# shift_register_pcb.net
KiCad netlist of a schematic drawn in Altium Designer
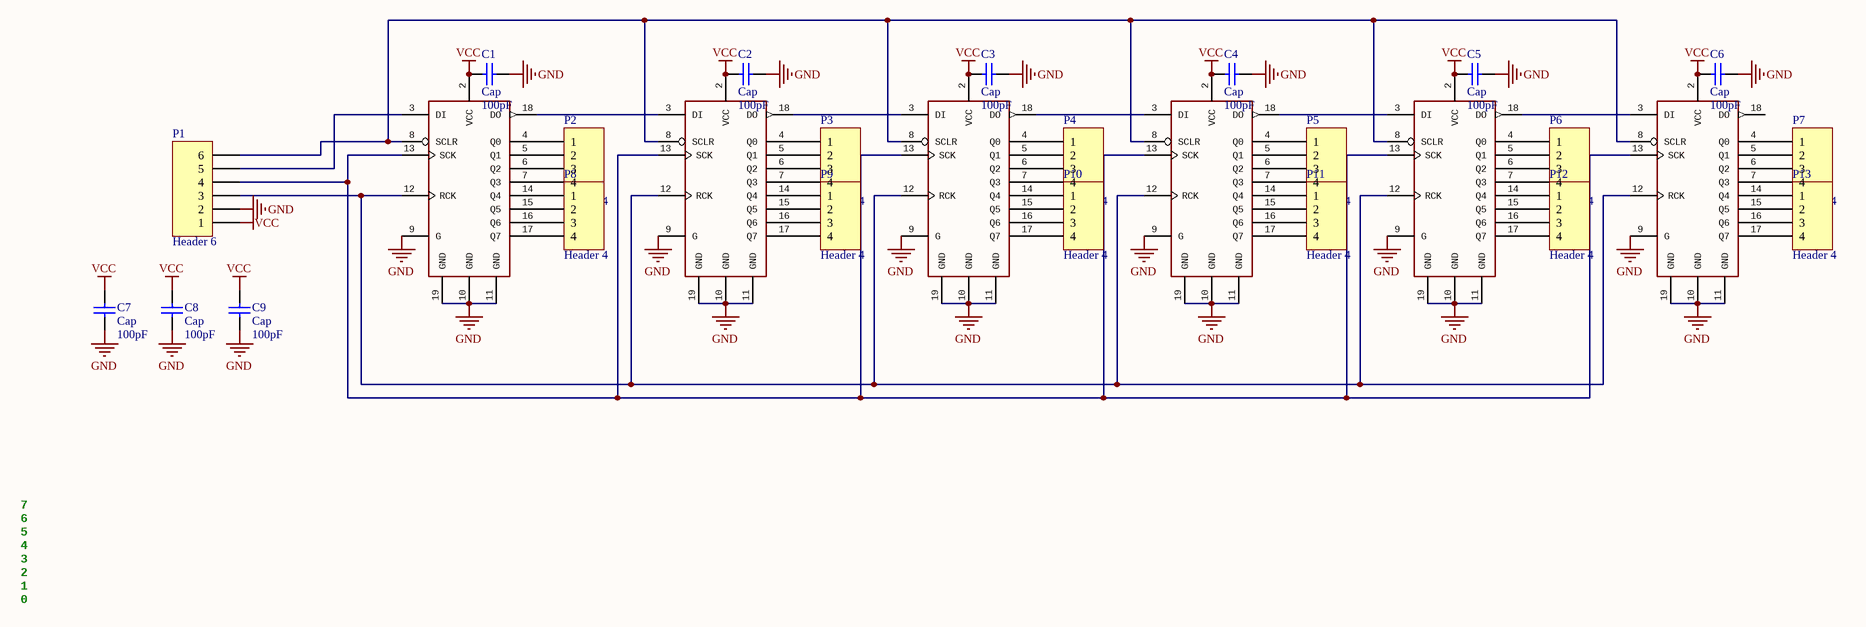
[diagram p0: shift register pcb.SchDoc]

(export (version "E")
  (design (tool "Eeschema 10.0.6"))
  (components
    (comp (ref "C1")
      (value "Cap")
      (footprint "RAD-0.3")
      (description "Capacitor")
      (fields (field (name "ALTIUM_VALUE") "100pF") (field (name "PUBLISHER") "Altium Limited"))
      (libsource (lib "Miscellaneous Devices") (part "Cap"))
    )
    (comp (ref "C2")
      (value "Cap")
      (footprint "RAD-0.3")
      (description "Capacitor")
      (fields (field (name "ALTIUM_VALUE") "100pF") (field (name "PUBLISHER") "Altium Limited"))
      (libsource (lib "Miscellaneous Devices") (part "Cap"))
    )
    (comp (ref "C3")
      (value "Cap")
      (footprint "RAD-0.3")
      (description "Capacitor")
      (fields (field (name "ALTIUM_VALUE") "100pF") (field (name "PUBLISHER") "Altium Limited"))
      (libsource (lib "Miscellaneous Devices") (part "Cap"))
    )
    (comp (ref "C4")
      (value "Cap")
      (footprint "RAD-0.3")
      (description "Capacitor")
      (fields (field (name "ALTIUM_VALUE") "100pF") (field (name "PUBLISHER") "Altium Limited"))
      (libsource (lib "Miscellaneous Devices") (part "Cap"))
    )
    (comp (ref "C5")
      (value "Cap")
      (footprint "RAD-0.3")
      (description "Capacitor")
      (fields (field (name "ALTIUM_VALUE") "100pF") (field (name "PUBLISHER") "Altium Limited"))
      (libsource (lib "Miscellaneous Devices") (part "Cap"))
    )
    (comp (ref "C6")
      (value "Cap")
      (footprint "RAD-0.3")
      (description "Capacitor")
      (fields (field (name "ALTIUM_VALUE") "100pF") (field (name "PUBLISHER") "Altium Limited"))
      (libsource (lib "Miscellaneous Devices") (part "Cap"))
    )
    (comp (ref "C7")
      (value "Cap")
      (footprint "RAD-0.3")
      (description "Capacitor")
      (fields (field (name "ALTIUM_VALUE") "100pF") (field (name "PUBLISHER") "Altium Limited"))
      (libsource (lib "Miscellaneous Devices") (part "Cap"))
    )
    (comp (ref "C8")
      (value "Cap")
      (footprint "RAD-0.3")
      (description "Capacitor")
      (fields (field (name "ALTIUM_VALUE") "100pF") (field (name "PUBLISHER") "Altium Limited"))
      (libsource (lib "Miscellaneous Devices") (part "Cap"))
    )
    (comp (ref "C9")
      (value "Cap")
      (footprint "RAD-0.3")
      (description "Capacitor")
      (fields (field (name "ALTIUM_VALUE") "100pF") (field (name "PUBLISHER") "Altium Limited"))
      (libsource (lib "Miscellaneous Devices") (part "Cap"))
    )
    (comp (ref "IC1") (value "TPIC6B596N") (footprint "PDIP20") (libsource (lib "tpic") (part "TPIC6B596N")))
    (comp (ref "IC2") (value "TPIC6B596N") (footprint "PDIP20") (libsource (lib "tpic") (part "TPIC6B596N")))
    (comp (ref "IC3") (value "TPIC6B596N") (footprint "PDIP20") (libsource (lib "tpic") (part "TPIC6B596N")))
    (comp (ref "IC4") (value "TPIC6B596N") (footprint "PDIP20") (libsource (lib "tpic") (part "TPIC6B596N")))
    (comp (ref "IC5") (value "TPIC6B596N") (footprint "PDIP20") (libsource (lib "tpic") (part "TPIC6B596N")))
    (comp (ref "IC6") (value "TPIC6B596N") (footprint "PDIP20") (libsource (lib "tpic") (part "TPIC6B596N")))
    (comp (ref "P1")
      (value "Header 6")
      (footprint "HDR1X6")
      (description "Header, 6-Pin")
      (fields (field (name "PUBLISHER") "Altium Limited"))
      (libsource (lib "Miscellaneous Connectors") (part "Header 6"))
    )
    (comp (ref "P2")
      (value "Header 4")
      (footprint "HDR1X4")
      (description "Header, 4-Pin")
      (fields (field (name "PUBLISHER") "Altium Limited"))
      (libsource (lib "Miscellaneous Connectors") (part "Header 4"))
    )
    (comp (ref "P3")
      (value "Header 4")
      (footprint "HDR1X4")
      (description "Header, 4-Pin")
      (fields (field (name "PUBLISHER") "Altium Limited"))
      (libsource (lib "Miscellaneous Connectors") (part "Header 4"))
    )
    (comp (ref "P4")
      (value "Header 4")
      (footprint "HDR1X4")
      (description "Header, 4-Pin")
      (fields (field (name "PUBLISHER") "Altium Limited"))
      (libsource (lib "Miscellaneous Connectors") (part "Header 4"))
    )
    (comp (ref "P5")
      (value "Header 4")
      (footprint "HDR1X4")
      (description "Header, 4-Pin")
      (fields (field (name "PUBLISHER") "Altium Limited"))
      (libsource (lib "Miscellaneous Connectors") (part "Header 4"))
    )
    (comp (ref "P6")
      (value "Header 4")
      (footprint "HDR1X4")
      (description "Header, 4-Pin")
      (fields (field (name "PUBLISHER") "Altium Limited"))
      (libsource (lib "Miscellaneous Connectors") (part "Header 4"))
    )
    (comp (ref "P7")
      (value "Header 4")
      (footprint "HDR1X4")
      (description "Header, 4-Pin")
      (fields (field (name "PUBLISHER") "Altium Limited"))
      (libsource (lib "Miscellaneous Connectors") (part "Header 4"))
    )
    (comp (ref "P8")
      (value "Header 4")
      (footprint "HDR1X4")
      (description "Header, 4-Pin")
      (fields (field (name "PUBLISHER") "Altium Limited"))
      (libsource (lib "Miscellaneous Connectors") (part "Header 4"))
    )
    (comp (ref "P9")
      (value "Header 4")
      (footprint "HDR1X4")
      (description "Header, 4-Pin")
      (fields (field (name "PUBLISHER") "Altium Limited"))
      (libsource (lib "Miscellaneous Connectors") (part "Header 4"))
    )
    (comp (ref "P10")
      (value "Header 4")
      (footprint "HDR1X4")
      (description "Header, 4-Pin")
      (fields (field (name "PUBLISHER") "Altium Limited"))
      (libsource (lib "Miscellaneous Connectors") (part "Header 4"))
    )
    (comp (ref "P11")
      (value "Header 4")
      (footprint "HDR1X4")
      (description "Header, 4-Pin")
      (fields (field (name "PUBLISHER") "Altium Limited"))
      (libsource (lib "Miscellaneous Connectors") (part "Header 4"))
    )
    (comp (ref "P12")
      (value "Header 4")
      (footprint "HDR1X4")
      (description "Header, 4-Pin")
      (fields (field (name "PUBLISHER") "Altium Limited"))
      (libsource (lib "Miscellaneous Connectors") (part "Header 4"))
    )
    (comp (ref "P13")
      (value "Header 4")
      (footprint "HDR1X4")
      (description "Header, 4-Pin")
      (fields (field (name "PUBLISHER") "Altium Limited"))
      (libsource (lib "Miscellaneous Connectors") (part "Header 4"))
    )
  )
  (nets
    (net (code "1") (name "GND") (class "Default")
      (node (ref "C1") (pin "1") (pinfunction "1_1") (pintype "passive"))
      (node (ref "C2") (pin "1") (pinfunction "1_1") (pintype "passive"))
      (node (ref "C3") (pin "1") (pinfunction "1_1") (pintype "passive"))
      (node (ref "C4") (pin "1") (pinfunction "1_1") (pintype "passive"))
      (node (ref "C5") (pin "1") (pinfunction "1_1") (pintype "passive"))
      (node (ref "C6") (pin "1") (pinfunction "1_1") (pintype "passive"))
      (node (ref "C7") (pin "2") (pinfunction "2_2") (pintype "passive"))
      (node (ref "C8") (pin "2") (pinfunction "2_2") (pintype "passive"))
      (node (ref "C9") (pin "2") (pinfunction "2_2") (pintype "passive"))
      (node (ref "IC1") (pin "10") (pinfunction "GND_10") (pintype "power_in"))
      (node (ref "IC1") (pin "11") (pinfunction "GND_11") (pintype "power_in"))
      (node (ref "IC1") (pin "19") (pinfunction "GND_19") (pintype "power_in"))
      (node (ref "IC1") (pin "9") (pinfunction "G_9") (pintype "passive"))
      (node (ref "IC2") (pin "10") (pinfunction "GND_10") (pintype "power_in"))
      (node (ref "IC2") (pin "11") (pinfunction "GND_11") (pintype "power_in"))
      (node (ref "IC2") (pin "19") (pinfunction "GND_19") (pintype "power_in"))
      (node (ref "IC2") (pin "9") (pinfunction "G_9") (pintype "passive"))
      (node (ref "IC3") (pin "10") (pinfunction "GND_10") (pintype "power_in"))
      (node (ref "IC3") (pin "11") (pinfunction "GND_11") (pintype "power_in"))
      (node (ref "IC3") (pin "19") (pinfunction "GND_19") (pintype "power_in"))
      (node (ref "IC3") (pin "9") (pinfunction "G_9") (pintype "passive"))
      (node (ref "IC4") (pin "10") (pinfunction "GND_10") (pintype "power_in"))
      (node (ref "IC4") (pin "11") (pinfunction "GND_11") (pintype "power_in"))
      (node (ref "IC4") (pin "19") (pinfunction "GND_19") (pintype "power_in"))
      (node (ref "IC4") (pin "9") (pinfunction "G_9") (pintype "passive"))
      (node (ref "IC5") (pin "10") (pinfunction "GND_10") (pintype "power_in"))
      (node (ref "IC5") (pin "11") (pinfunction "GND_11") (pintype "power_in"))
      (node (ref "IC5") (pin "19") (pinfunction "GND_19") (pintype "power_in"))
      (node (ref "IC5") (pin "9") (pinfunction "G_9") (pintype "passive"))
      (node (ref "IC6") (pin "10") (pinfunction "GND_10") (pintype "power_in"))
      (node (ref "IC6") (pin "11") (pinfunction "GND_11") (pintype "power_in"))
      (node (ref "IC6") (pin "19") (pinfunction "GND_19") (pintype "power_in"))
      (node (ref "IC6") (pin "9") (pinfunction "G_9") (pintype "passive"))
      (node (ref "P1") (pin "2") (pinfunction "2_2") (pintype "passive"))
    )
    (net (code "2") (name "Net-(IC1-DI)") (class "Default")
      (node (ref "IC1") (pin "3") (pinfunction "DI_3") (pintype "passive"))
      (node (ref "P1") (pin "5") (pinfunction "5_5") (pintype "passive"))
    )
    (net (code "3") (name "Net-(IC1-DO)") (class "Default")
      (node (ref "IC1") (pin "18") (pinfunction "DO_18") (pintype "output"))
      (node (ref "IC2") (pin "3") (pinfunction "DI_3") (pintype "passive"))
    )
    (net (code "4") (name "Net-(IC1-Q0)") (class "Default")
      (node (ref "IC1") (pin "4") (pinfunction "Q0_4") (pintype "open_collector"))
      (node (ref "P2") (pin "1") (pinfunction "1_1") (pintype "passive"))
    )
    (net (code "5") (name "Net-(IC1-Q1)") (class "Default")
      (node (ref "IC1") (pin "5") (pinfunction "Q1_5") (pintype "open_collector"))
      (node (ref "P2") (pin "2") (pinfunction "2_2") (pintype "passive"))
    )
    (net (code "6") (name "Net-(IC1-Q2)") (class "Default")
      (node (ref "IC1") (pin "6") (pinfunction "Q2_6") (pintype "open_collector"))
      (node (ref "P2") (pin "3") (pinfunction "3_3") (pintype "passive"))
    )
    (net (code "7") (name "Net-(IC1-Q3)") (class "Default")
      (node (ref "IC1") (pin "7") (pinfunction "Q3_7") (pintype "open_collector"))
      (node (ref "P2") (pin "4") (pinfunction "4_4") (pintype "passive"))
    )
    (net (code "8") (name "Net-(IC1-Q4)") (class "Default")
      (node (ref "IC1") (pin "14") (pinfunction "Q4_14") (pintype "open_collector"))
      (node (ref "P8") (pin "1") (pinfunction "1_1") (pintype "passive"))
    )
    (net (code "9") (name "Net-(IC1-Q5)") (class "Default")
      (node (ref "IC1") (pin "15") (pinfunction "Q5_15") (pintype "open_collector"))
      (node (ref "P8") (pin "2") (pinfunction "2_2") (pintype "passive"))
    )
    (net (code "10") (name "Net-(IC1-Q6)") (class "Default")
      (node (ref "IC1") (pin "16") (pinfunction "Q6_16") (pintype "open_collector"))
      (node (ref "P8") (pin "3") (pinfunction "3_3") (pintype "passive"))
    )
    (net (code "11") (name "Net-(IC1-Q7)") (class "Default")
      (node (ref "IC1") (pin "17") (pinfunction "Q7_17") (pintype "open_collector"))
      (node (ref "P8") (pin "4") (pinfunction "4_4") (pintype "passive"))
    )
    (net (code "12") (name "Net-(IC1-RCK)") (class "Default")
      (node (ref "IC1") (pin "12") (pinfunction "RCK_12") (pintype "passive"))
      (node (ref "IC2") (pin "12") (pinfunction "RCK_12") (pintype "passive"))
      (node (ref "IC3") (pin "12") (pinfunction "RCK_12") (pintype "passive"))
      (node (ref "IC4") (pin "12") (pinfunction "RCK_12") (pintype "passive"))
      (node (ref "IC5") (pin "12") (pinfunction "RCK_12") (pintype "passive"))
      (node (ref "IC6") (pin "12") (pinfunction "RCK_12") (pintype "passive"))
      (node (ref "P1") (pin "3") (pinfunction "3_3") (pintype "passive"))
    )
    (net (code "13") (name "Net-(IC1-SCK)") (class "Default")
      (node (ref "IC1") (pin "13") (pinfunction "SCK_13") (pintype "passive"))
      (node (ref "IC2") (pin "13") (pinfunction "SCK_13") (pintype "passive"))
      (node (ref "IC3") (pin "13") (pinfunction "SCK_13") (pintype "passive"))
      (node (ref "IC4") (pin "13") (pinfunction "SCK_13") (pintype "passive"))
      (node (ref "IC5") (pin "13") (pinfunction "SCK_13") (pintype "passive"))
      (node (ref "IC6") (pin "13") (pinfunction "SCK_13") (pintype "passive"))
      (node (ref "P1") (pin "4") (pinfunction "4_4") (pintype "passive"))
    )
    (net (code "14") (name "Net-(IC1-SCLR)") (class "Default")
      (node (ref "IC1") (pin "8") (pinfunction "SCLR_8") (pintype "passive"))
      (node (ref "IC2") (pin "8") (pinfunction "SCLR_8") (pintype "passive"))
      (node (ref "IC3") (pin "8") (pinfunction "SCLR_8") (pintype "passive"))
      (node (ref "IC4") (pin "8") (pinfunction "SCLR_8") (pintype "passive"))
      (node (ref "IC5") (pin "8") (pinfunction "SCLR_8") (pintype "passive"))
      (node (ref "IC6") (pin "8") (pinfunction "SCLR_8") (pintype "passive"))
      (node (ref "P1") (pin "6") (pinfunction "6_6") (pintype "passive"))
    )
    (net (code "15") (name "Net-(IC2-DO)") (class "Default")
      (node (ref "IC2") (pin "18") (pinfunction "DO_18") (pintype "output"))
      (node (ref "IC3") (pin "3") (pinfunction "DI_3") (pintype "passive"))
    )
    (net (code "16") (name "Net-(IC2-Q0)") (class "Default")
      (node (ref "IC2") (pin "4") (pinfunction "Q0_4") (pintype "open_collector"))
      (node (ref "P3") (pin "1") (pinfunction "1_1") (pintype "passive"))
    )
    (net (code "17") (name "Net-(IC2-Q1)") (class "Default")
      (node (ref "IC2") (pin "5") (pinfunction "Q1_5") (pintype "open_collector"))
      (node (ref "P3") (pin "2") (pinfunction "2_2") (pintype "passive"))
    )
    (net (code "18") (name "Net-(IC2-Q2)") (class "Default")
      (node (ref "IC2") (pin "6") (pinfunction "Q2_6") (pintype "open_collector"))
      (node (ref "P3") (pin "3") (pinfunction "3_3") (pintype "passive"))
    )
    (net (code "19") (name "Net-(IC2-Q3)") (class "Default")
      (node (ref "IC2") (pin "7") (pinfunction "Q3_7") (pintype "open_collector"))
      (node (ref "P3") (pin "4") (pinfunction "4_4") (pintype "passive"))
    )
    (net (code "20") (name "Net-(IC2-Q4)") (class "Default")
      (node (ref "IC2") (pin "14") (pinfunction "Q4_14") (pintype "open_collector"))
      (node (ref "P9") (pin "1") (pinfunction "1_1") (pintype "passive"))
    )
    (net (code "21") (name "Net-(IC2-Q5)") (class "Default")
      (node (ref "IC2") (pin "15") (pinfunction "Q5_15") (pintype "open_collector"))
      (node (ref "P9") (pin "2") (pinfunction "2_2") (pintype "passive"))
    )
    (net (code "22") (name "Net-(IC2-Q6)") (class "Default")
      (node (ref "IC2") (pin "16") (pinfunction "Q6_16") (pintype "open_collector"))
      (node (ref "P9") (pin "3") (pinfunction "3_3") (pintype "passive"))
    )
    (net (code "23") (name "Net-(IC2-Q7)") (class "Default")
      (node (ref "IC2") (pin "17") (pinfunction "Q7_17") (pintype "open_collector"))
      (node (ref "P9") (pin "4") (pinfunction "4_4") (pintype "passive"))
    )
    (net (code "24") (name "Net-(IC3-DO)") (class "Default")
      (node (ref "IC3") (pin "18") (pinfunction "DO_18") (pintype "output"))
      (node (ref "IC4") (pin "3") (pinfunction "DI_3") (pintype "passive"))
    )
    (net (code "25") (name "Net-(IC3-Q0)") (class "Default")
      (node (ref "IC3") (pin "4") (pinfunction "Q0_4") (pintype "open_collector"))
      (node (ref "P4") (pin "1") (pinfunction "1_1") (pintype "passive"))
    )
    (net (code "26") (name "Net-(IC3-Q1)") (class "Default")
      (node (ref "IC3") (pin "5") (pinfunction "Q1_5") (pintype "open_collector"))
      (node (ref "P4") (pin "2") (pinfunction "2_2") (pintype "passive"))
    )
    (net (code "27") (name "Net-(IC3-Q2)") (class "Default")
      (node (ref "IC3") (pin "6") (pinfunction "Q2_6") (pintype "open_collector"))
      (node (ref "P4") (pin "3") (pinfunction "3_3") (pintype "passive"))
    )
    (net (code "28") (name "Net-(IC3-Q3)") (class "Default")
      (node (ref "IC3") (pin "7") (pinfunction "Q3_7") (pintype "open_collector"))
      (node (ref "P4") (pin "4") (pinfunction "4_4") (pintype "passive"))
    )
    (net (code "29") (name "Net-(IC3-Q4)") (class "Default")
      (node (ref "IC3") (pin "14") (pinfunction "Q4_14") (pintype "open_collector"))
      (node (ref "P10") (pin "1") (pinfunction "1_1") (pintype "passive"))
    )
    (net (code "30") (name "Net-(IC3-Q5)") (class "Default")
      (node (ref "IC3") (pin "15") (pinfunction "Q5_15") (pintype "open_collector"))
      (node (ref "P10") (pin "2") (pinfunction "2_2") (pintype "passive"))
    )
    (net (code "31") (name "Net-(IC3-Q6)") (class "Default")
      (node (ref "IC3") (pin "16") (pinfunction "Q6_16") (pintype "open_collector"))
      (node (ref "P10") (pin "3") (pinfunction "3_3") (pintype "passive"))
    )
    (net (code "32") (name "Net-(IC3-Q7)") (class "Default")
      (node (ref "IC3") (pin "17") (pinfunction "Q7_17") (pintype "open_collector"))
      (node (ref "P10") (pin "4") (pinfunction "4_4") (pintype "passive"))
    )
    (net (code "33") (name "Net-(IC4-DO)") (class "Default")
      (node (ref "IC4") (pin "18") (pinfunction "DO_18") (pintype "output"))
      (node (ref "IC5") (pin "3") (pinfunction "DI_3") (pintype "passive"))
    )
    (net (code "34") (name "Net-(IC4-Q0)") (class "Default")
      (node (ref "IC4") (pin "4") (pinfunction "Q0_4") (pintype "open_collector"))
      (node (ref "P5") (pin "1") (pinfunction "1_1") (pintype "passive"))
    )
    (net (code "35") (name "Net-(IC4-Q1)") (class "Default")
      (node (ref "IC4") (pin "5") (pinfunction "Q1_5") (pintype "open_collector"))
      (node (ref "P5") (pin "2") (pinfunction "2_2") (pintype "passive"))
    )
    (net (code "36") (name "Net-(IC4-Q2)") (class "Default")
      (node (ref "IC4") (pin "6") (pinfunction "Q2_6") (pintype "open_collector"))
      (node (ref "P5") (pin "3") (pinfunction "3_3") (pintype "passive"))
    )
    (net (code "37") (name "Net-(IC4-Q3)") (class "Default")
      (node (ref "IC4") (pin "7") (pinfunction "Q3_7") (pintype "open_collector"))
      (node (ref "P5") (pin "4") (pinfunction "4_4") (pintype "passive"))
    )
    (net (code "38") (name "Net-(IC4-Q4)") (class "Default")
      (node (ref "IC4") (pin "14") (pinfunction "Q4_14") (pintype "open_collector"))
      (node (ref "P11") (pin "1") (pinfunction "1_1") (pintype "passive"))
    )
    (net (code "39") (name "Net-(IC4-Q5)") (class "Default")
      (node (ref "IC4") (pin "15") (pinfunction "Q5_15") (pintype "open_collector"))
      (node (ref "P11") (pin "2") (pinfunction "2_2") (pintype "passive"))
    )
    (net (code "40") (name "Net-(IC4-Q6)") (class "Default")
      (node (ref "IC4") (pin "16") (pinfunction "Q6_16") (pintype "open_collector"))
      (node (ref "P11") (pin "3") (pinfunction "3_3") (pintype "passive"))
    )
    (net (code "41") (name "Net-(IC4-Q7)") (class "Default")
      (node (ref "IC4") (pin "17") (pinfunction "Q7_17") (pintype "open_collector"))
      (node (ref "P11") (pin "4") (pinfunction "4_4") (pintype "passive"))
    )
    (net (code "42") (name "Net-(IC5-DO)") (class "Default")
      (node (ref "IC5") (pin "18") (pinfunction "DO_18") (pintype "output"))
      (node (ref "IC6") (pin "3") (pinfunction "DI_3") (pintype "passive"))
    )
    (net (code "43") (name "Net-(IC5-Q0)") (class "Default")
      (node (ref "IC5") (pin "4") (pinfunction "Q0_4") (pintype "open_collector"))
      (node (ref "P6") (pin "1") (pinfunction "1_1") (pintype "passive"))
    )
    (net (code "44") (name "Net-(IC5-Q1)") (class "Default")
      (node (ref "IC5") (pin "5") (pinfunction "Q1_5") (pintype "open_collector"))
      (node (ref "P6") (pin "2") (pinfunction "2_2") (pintype "passive"))
    )
    (net (code "45") (name "Net-(IC5-Q2)") (class "Default")
      (node (ref "IC5") (pin "6") (pinfunction "Q2_6") (pintype "open_collector"))
      (node (ref "P6") (pin "3") (pinfunction "3_3") (pintype "passive"))
    )
    (net (code "46") (name "Net-(IC5-Q3)") (class "Default")
      (node (ref "IC5") (pin "7") (pinfunction "Q3_7") (pintype "open_collector"))
      (node (ref "P6") (pin "4") (pinfunction "4_4") (pintype "passive"))
    )
    (net (code "47") (name "Net-(IC5-Q4)") (class "Default")
      (node (ref "IC5") (pin "14") (pinfunction "Q4_14") (pintype "open_collector"))
      (node (ref "P12") (pin "1") (pinfunction "1_1") (pintype "passive"))
    )
    (net (code "48") (name "Net-(IC5-Q5)") (class "Default")
      (node (ref "IC5") (pin "15") (pinfunction "Q5_15") (pintype "open_collector"))
      (node (ref "P12") (pin "2") (pinfunction "2_2") (pintype "passive"))
    )
    (net (code "49") (name "Net-(IC5-Q6)") (class "Default")
      (node (ref "IC5") (pin "16") (pinfunction "Q6_16") (pintype "open_collector"))
      (node (ref "P12") (pin "3") (pinfunction "3_3") (pintype "passive"))
    )
    (net (code "50") (name "Net-(IC5-Q7)") (class "Default")
      (node (ref "IC5") (pin "17") (pinfunction "Q7_17") (pintype "open_collector"))
      (node (ref "P12") (pin "4") (pinfunction "4_4") (pintype "passive"))
    )
    (net (code "51") (name "Net-(IC6-Q0)") (class "Default")
      (node (ref "IC6") (pin "4") (pinfunction "Q0_4") (pintype "open_collector"))
      (node (ref "P7") (pin "1") (pinfunction "1_1") (pintype "passive"))
    )
    (net (code "52") (name "Net-(IC6-Q1)") (class "Default")
      (node (ref "IC6") (pin "5") (pinfunction "Q1_5") (pintype "open_collector"))
      (node (ref "P7") (pin "2") (pinfunction "2_2") (pintype "passive"))
    )
    (net (code "53") (name "Net-(IC6-Q2)") (class "Default")
      (node (ref "IC6") (pin "6") (pinfunction "Q2_6") (pintype "open_collector"))
      (node (ref "P7") (pin "3") (pinfunction "3_3") (pintype "passive"))
    )
    (net (code "54") (name "Net-(IC6-Q3)") (class "Default")
      (node (ref "IC6") (pin "7") (pinfunction "Q3_7") (pintype "open_collector"))
      (node (ref "P7") (pin "4") (pinfunction "4_4") (pintype "passive"))
    )
    (net (code "55") (name "Net-(IC6-Q4)") (class "Default")
      (node (ref "IC6") (pin "14") (pinfunction "Q4_14") (pintype "open_collector"))
      (node (ref "P13") (pin "1") (pinfunction "1_1") (pintype "passive"))
    )
    (net (code "56") (name "Net-(IC6-Q5)") (class "Default")
      (node (ref "IC6") (pin "15") (pinfunction "Q5_15") (pintype "open_collector"))
      (node (ref "P13") (pin "2") (pinfunction "2_2") (pintype "passive"))
    )
    (net (code "57") (name "Net-(IC6-Q6)") (class "Default")
      (node (ref "IC6") (pin "16") (pinfunction "Q6_16") (pintype "open_collector"))
      (node (ref "P13") (pin "3") (pinfunction "3_3") (pintype "passive"))
    )
    (net (code "58") (name "Net-(IC6-Q7)") (class "Default")
      (node (ref "IC6") (pin "17") (pinfunction "Q7_17") (pintype "open_collector"))
      (node (ref "P13") (pin "4") (pinfunction "4_4") (pintype "passive"))
    )
    (net (code "59") (name "VCC") (class "Default")
      (node (ref "C1") (pin "2") (pinfunction "2_2") (pintype "passive"))
      (node (ref "C2") (pin "2") (pinfunction "2_2") (pintype "passive"))
      (node (ref "C3") (pin "2") (pinfunction "2_2") (pintype "passive"))
      (node (ref "C4") (pin "2") (pinfunction "2_2") (pintype "passive"))
      (node (ref "C5") (pin "2") (pinfunction "2_2") (pintype "passive"))
      (node (ref "C6") (pin "2") (pinfunction "2_2") (pintype "passive"))
      (node (ref "C7") (pin "1") (pinfunction "1_1") (pintype "passive"))
      (node (ref "C8") (pin "1") (pinfunction "1_1") (pintype "passive"))
      (node (ref "C9") (pin "1") (pinfunction "1_1") (pintype "passive"))
      (node (ref "IC1") (pin "2") (pinfunction "VCC_2") (pintype "power_in"))
      (node (ref "IC2") (pin "2") (pinfunction "VCC_2") (pintype "power_in"))
      (node (ref "IC3") (pin "2") (pinfunction "VCC_2") (pintype "power_in"))
      (node (ref "IC4") (pin "2") (pinfunction "VCC_2") (pintype "power_in"))
      (node (ref "IC5") (pin "2") (pinfunction "VCC_2") (pintype "power_in"))
      (node (ref "IC6") (pin "2") (pinfunction "VCC_2") (pintype "power_in"))
      (node (ref "P1") (pin "1") (pinfunction "1_1") (pintype "passive"))
    )
    (net (code "60") (name "unconnected-(IC6-DO-Pad18)") (class "Default")
      (node (ref "IC6") (pin "18") (pinfunction "DO_18") (pintype "output"))
    )
  )
)
